# Sheet2.net
KiCad netlist of a schematic drawn in Altium Designer
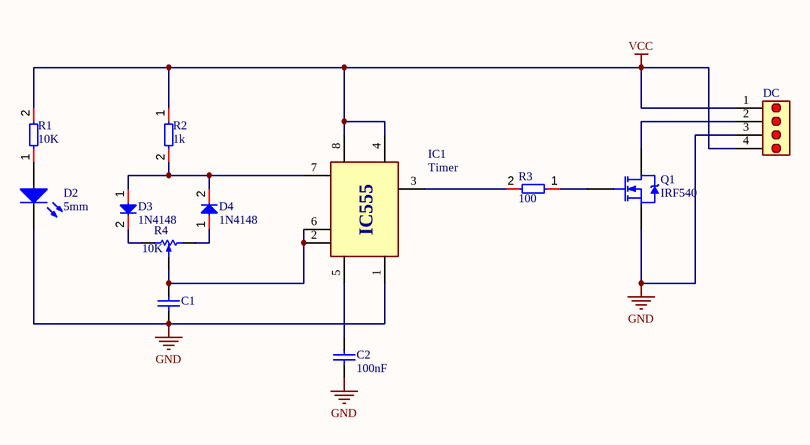
[diagram p0: Sheet2.SchDoc]

(export (version "E")
  (design (tool "Eeschema 10.0.6"))
  (components
    (comp (ref "C1")
      (value "SMD 0603")
      (footprint "SMD CAPACITOR0805")
      (libsource (lib "Library 3D") (part "CAP SMD"))
    )
    (comp (ref "C2")
      (value "100nF")
      (footprint "CN5")
      (fields (field (name "PUBLISHER") "Altium Limited"))
      (libsource (lib "Library 3D") (part "CN 33pF"))
    )
    (comp (ref "D2") (value "5mm") (footprint "LED 5mm BLUE") (libsource (lib "Library 3D") (part "LED 5mm")))
    (comp (ref "D3")
      (value "1N4148")
      (footprint "SOD-80")
      (libsource (lib "SMDLibrary") (part "Diode 1N4148"))
    )
    (comp (ref "D4")
      (value "1N4148")
      (footprint "SOD-80")
      (libsource (lib "SMDLibrary") (part "Diode 1N4148"))
    )
    (comp (ref "DC")
      (value "Header 4")
      (footprint "HEADER 4")
      (libsource (lib "Library 3D") (part "Header 4"))
    )
    (comp (ref "IC1") (value "Timer") (footprint "DIP8") (libsource (lib "Library 3D") (part "555")))
    (comp (ref "Q1") (value "IRF540") (footprint "TO220A") (libsource (lib "Library 3D") (part "IRF540")))
    (comp (ref "R1")
      (value "10K")
      (footprint "RES-0.25W-H-MF")
      (libsource (lib "SMDLibrary") (part "Resistors THD"))
    )
    (comp (ref "R2") (value "1k") (footprint "RES-0.25W-H-MF") (libsource (lib "") (part "Resistors THD_1")))
    (comp (ref "R3") (value "100") (footprint "RES-0.25W-H-MF") (libsource (lib "") (part "Resistors THD_2")))
    (comp (ref "R4") (value "10K") (footprint "VOLUME2") (libsource (lib "Library 3D") (part "Res Variable")))
  )
  (nets
    (net (code "1") (name "GND") (class "Default")
      (node (ref "C1") (pin "1") (pinfunction "1_1") (pintype "passive"))
      (node (ref "C2") (pin "1") (pinfunction "1_1") (pintype "passive"))
      (node (ref "D2") (pin "2") (pinfunction "K_2") (pintype "passive"))
      (node (ref "DC") (pin "3") (pinfunction "3_3") (pintype "passive"))
      (node (ref "IC1") (pin "1") (pinfunction "1_1") (pintype "passive"))
      (node (ref "Q1") (pin "3") (pinfunction "S_3") (pintype "passive"))
    )
    (net (code "2") (name "Net-(C2-Pad2)") (class "Default")
      (node (ref "C2") (pin "2") (pinfunction "2_2") (pintype "passive"))
      (node (ref "IC1") (pin "5") (pinfunction "5_5") (pintype "passive"))
    )
    (net (code "3") (name "Net-(D2-A)") (class "Default")
      (node (ref "D2") (pin "1") (pinfunction "A_1") (pintype "passive"))
      (node (ref "R1") (pin "1") (pinfunction "1_1") (pintype "passive"))
    )
    (net (code "4") (name "Net-(D3-Pad1)") (class "Default")
      (node (ref "D3") (pin "1") (pinfunction "1_1") (pintype "passive"))
      (node (ref "D4") (pin "2") (pinfunction "2_2") (pintype "passive"))
      (node (ref "IC1") (pin "7") (pinfunction "7_7") (pintype "passive"))
      (node (ref "R2") (pin "2") (pinfunction "2_2") (pintype "passive"))
    )
    (net (code "5") (name "Net-(IC1-Pad3)") (class "Default")
      (node (ref "IC1") (pin "3") (pinfunction "3_3") (pintype "passive"))
      (node (ref "R3") (pin "2") (pinfunction "2_2") (pintype "passive"))
    )
    (net (code "6") (name "Net-(Q1-D)") (class "Default")
      (node (ref "DC") (pin "2") (pinfunction "2_2") (pintype "passive"))
      (node (ref "Q1") (pin "2") (pinfunction "D_2") (pintype "passive"))
    )
    (net (code "7") (name "Net-(Q1-G)") (class "Default")
      (node (ref "Q1") (pin "1") (pinfunction "G_1") (pintype "passive"))
      (node (ref "R3") (pin "1") (pinfunction "1_1") (pintype "passive"))
    )
    (net (code "8") (name "Net-(R4-+)") (class "Default")
      (node (ref "D4") (pin "1") (pinfunction "1_1") (pintype "passive"))
      (node (ref "R4") (pin "1") (pinfunction "+_1") (pintype "passive"))
    )
    (net (code "9") (name "Net-(R4--)") (class "Default")
      (node (ref "D3") (pin "2") (pinfunction "2_2") (pintype "passive"))
      (node (ref "R4") (pin "3") (pinfunction "-_3") (pintype "passive"))
    )
    (net (code "10") (name "Net-(R4-W)") (class "Default")
      (node (ref "C1") (pin "2") (pinfunction "2_2") (pintype "passive"))
      (node (ref "IC1") (pin "2") (pinfunction "2_2") (pintype "passive"))
      (node (ref "IC1") (pin "6") (pinfunction "6_6") (pintype "passive"))
      (node (ref "R4") (pin "2") (pinfunction "W_2") (pintype "passive"))
    )
    (net (code "11") (name "VCC") (class "Default")
      (node (ref "DC") (pin "1") (pinfunction "1_1") (pintype "passive"))
      (node (ref "DC") (pin "4") (pinfunction "4_4") (pintype "passive"))
      (node (ref "IC1") (pin "4") (pinfunction "4_4") (pintype "passive"))
      (node (ref "IC1") (pin "8") (pinfunction "8_8") (pintype "passive"))
      (node (ref "R1") (pin "2") (pinfunction "2_2") (pintype "passive"))
      (node (ref "R2") (pin "1") (pinfunction "1_1") (pintype "passive"))
    )
  )
)
